# rbccpsiisc_nRF24Cheep.net
KiCad netlist of a schematic drawn in EAGLE
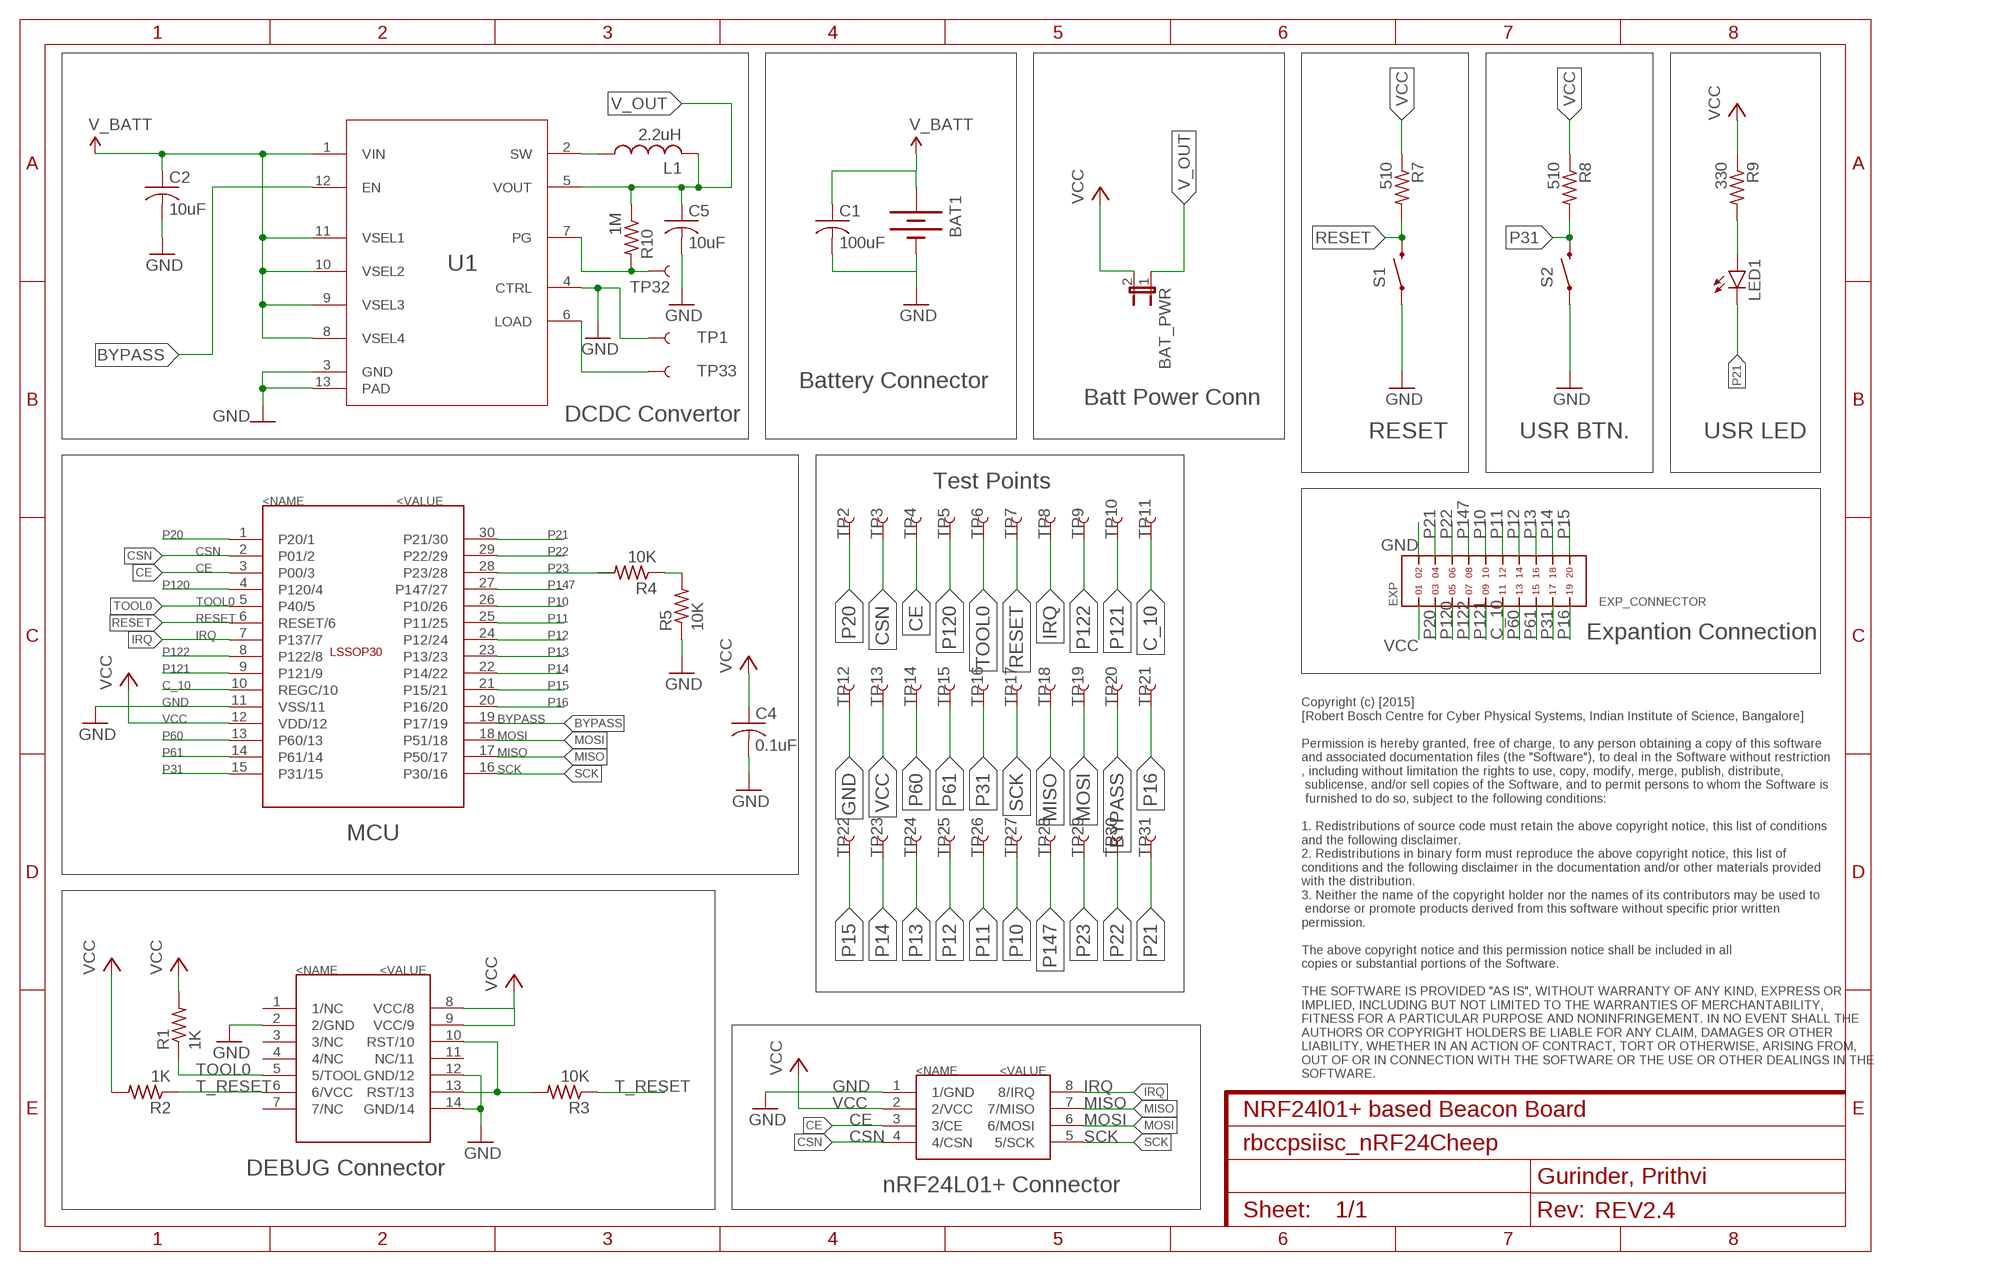
[diagram p0: schematic, sheet 1]

(export (version "E")
  (design (tool "Eeschema 10.0.6"))
  (components
    (comp (ref "BAT1")
      (value "BATTERY20SMD")
      (footprint "eagle-import:BATTCON_20MM")
      (libsource (lib "eagle-import") (part "BATTERY20SMD"))
    )
    (comp (ref "BAT_PWR")
      (value "JUMPER-2PTH")
      (footprint "eagle-import:1X02")
      (libsource (lib "eagle-import") (part "JUMPER-2PTH"))
    )
    (comp (ref "C1")
      (value "100uF")
      (footprint "eagle-import:C1206K")
      (libsource (lib "eagle-import") (part "C-USC1206K"))
    )
    (comp (ref "C2")
      (value "10uF")
      (footprint "eagle-import:C0603K")
      (libsource (lib "eagle-import") (part "C-USC0603K"))
    )
    (comp (ref "C4")
      (value "0.1uF")
      (footprint "eagle-import:C0603K")
      (libsource (lib "eagle-import") (part "C-USC0603K"))
    )
    (comp (ref "C5")
      (value "10uF")
      (footprint "eagle-import:C0603K")
      (libsource (lib "eagle-import") (part "C-USC0603K"))
    )
    (comp (ref "EXP")
      (value "EXP_CONNECTOR")
      (footprint "eagle-import:2X10")
      (libsource (lib "eagle-import") (part "2X10"))
    )
    (comp (ref "L1")
      (value "2.2uH")
      (footprint "eagle-import:L2012C")
      (libsource (lib "eagle-import") (part "L-USL2012C"))
    )
    (comp (ref "LED1")
      (value "LED0603")
      (footprint "eagle-import:LED-0603")
      (libsource (lib "eagle-import") (part "LED0603"))
    )
    (comp (ref "NRFSOCKET")
      (value "BERG_NRF24_NRF24")
      (footprint "eagle-import:BERG_NRF24_NRF24")
      (libsource (lib "eagle-import") (part "BERG_NRF24_NRF24"))
    )
    (comp (ref "R1")
      (value "1K")
      (footprint "eagle-import:R0603")
      (libsource (lib "eagle-import") (part "R-US_R0603"))
    )
    (comp (ref "R2")
      (value "1K")
      (footprint "eagle-import:R0603")
      (libsource (lib "eagle-import") (part "R-US_R0603"))
    )
    (comp (ref "R3")
      (value "10K")
      (footprint "eagle-import:R0603")
      (libsource (lib "eagle-import") (part "R-US_R0603"))
    )
    (comp (ref "R4")
      (value "10K")
      (footprint "eagle-import:R0603")
      (libsource (lib "eagle-import") (part "R-US_R0603"))
    )
    (comp (ref "R5")
      (value "10K")
      (footprint "eagle-import:R0603")
      (libsource (lib "eagle-import") (part "R-US_R0603"))
    )
    (comp (ref "R7")
      (value "510")
      (footprint "eagle-import:R0603")
      (libsource (lib "eagle-import") (part "R-US_R0603"))
    )
    (comp (ref "R8")
      (value "510")
      (footprint "eagle-import:R0603")
      (libsource (lib "eagle-import") (part "R-US_R0603"))
    )
    (comp (ref "R9")
      (value "330")
      (footprint "eagle-import:R0603")
      (libsource (lib "eagle-import") (part "R-US_R0603"))
    )
    (comp (ref "R10")
      (value "1M")
      (footprint "eagle-import:R0603")
      (libsource (lib "eagle-import") (part "R-US_R0603"))
    )
    (comp (ref "RENASENCE")
      (value "SSOP30_SSOP30")
      (footprint "eagle-import:SSOP30_SSOP30")
      (libsource (lib "eagle-import") (part "SSOP30_SSOP30"))
    )
    (comp (ref "S1")
      (value "SWITCH-MOMENTARY-2-SMD-1101NE")
      (footprint "eagle-import:TACTILE-SWITCH-1101NE")
      (libsource (lib "eagle-import") (part "SWITCH-MOMENTARY-2-SMD-1101NE"))
    )
    (comp (ref "S2")
      (value "SWITCH-MOMENTARY-2-SMD-1101NE")
      (footprint "eagle-import:TACTILE-SWITCH-1101NE")
      (libsource (lib "eagle-import") (part "SWITCH-MOMENTARY-2-SMD-1101NE"))
    )
    (comp (ref "TP1")
      (value "TEST-POINT3X4")
      (footprint "eagle-import:PAD.03X.04")
      (libsource (lib "eagle-import") (part "TEST-POINT3X4"))
    )
    (comp (ref "TP2")
      (value "TEST-POINT3X4")
      (footprint "eagle-import:PAD.03X.04")
      (libsource (lib "eagle-import") (part "TEST-POINT3X4"))
    )
    (comp (ref "TP3")
      (value "TEST-POINT3X4")
      (footprint "eagle-import:PAD.03X.04")
      (libsource (lib "eagle-import") (part "TEST-POINT3X4"))
    )
    (comp (ref "TP4")
      (value "TEST-POINT3X4")
      (footprint "eagle-import:PAD.03X.04")
      (libsource (lib "eagle-import") (part "TEST-POINT3X4"))
    )
    (comp (ref "TP5")
      (value "TEST-POINT3X4")
      (footprint "eagle-import:PAD.03X.04")
      (libsource (lib "eagle-import") (part "TEST-POINT3X4"))
    )
    (comp (ref "TP6")
      (value "TEST-POINT3X4")
      (footprint "eagle-import:PAD.03X.04")
      (libsource (lib "eagle-import") (part "TEST-POINT3X4"))
    )
    (comp (ref "TP7")
      (value "TEST-POINT3X4")
      (footprint "eagle-import:PAD.03X.04")
      (libsource (lib "eagle-import") (part "TEST-POINT3X4"))
    )
    (comp (ref "TP8")
      (value "TEST-POINT3X4")
      (footprint "eagle-import:PAD.03X.04")
      (libsource (lib "eagle-import") (part "TEST-POINT3X4"))
    )
    (comp (ref "TP9")
      (value "TEST-POINT3X4")
      (footprint "eagle-import:PAD.03X.04")
      (libsource (lib "eagle-import") (part "TEST-POINT3X4"))
    )
    (comp (ref "TP10")
      (value "TEST-POINT3X4")
      (footprint "eagle-import:PAD.03X.04")
      (libsource (lib "eagle-import") (part "TEST-POINT3X4"))
    )
    (comp (ref "TP11")
      (value "TEST-POINT3X4")
      (footprint "eagle-import:PAD.03X.04")
      (libsource (lib "eagle-import") (part "TEST-POINT3X4"))
    )
    (comp (ref "TP12")
      (value "TEST-POINT3X4")
      (footprint "eagle-import:PAD.03X.04")
      (libsource (lib "eagle-import") (part "TEST-POINT3X4"))
    )
    (comp (ref "TP13")
      (value "TEST-POINT3X4")
      (footprint "eagle-import:PAD.03X.04")
      (libsource (lib "eagle-import") (part "TEST-POINT3X4"))
    )
    (comp (ref "TP14")
      (value "TEST-POINT3X4")
      (footprint "eagle-import:PAD.03X.04")
      (libsource (lib "eagle-import") (part "TEST-POINT3X4"))
    )
    (comp (ref "TP15")
      (value "TEST-POINT3X4")
      (footprint "eagle-import:PAD.03X.04")
      (libsource (lib "eagle-import") (part "TEST-POINT3X4"))
    )
    (comp (ref "TP16")
      (value "TEST-POINT3X4")
      (footprint "eagle-import:PAD.03X.04")
      (libsource (lib "eagle-import") (part "TEST-POINT3X4"))
    )
    (comp (ref "TP17")
      (value "TEST-POINT3X4")
      (footprint "eagle-import:PAD.03X.04")
      (libsource (lib "eagle-import") (part "TEST-POINT3X4"))
    )
    (comp (ref "TP18")
      (value "TEST-POINT3X4")
      (footprint "eagle-import:PAD.03X.04")
      (libsource (lib "eagle-import") (part "TEST-POINT3X4"))
    )
    (comp (ref "TP19")
      (value "TEST-POINT3X4")
      (footprint "eagle-import:PAD.03X.04")
      (libsource (lib "eagle-import") (part "TEST-POINT3X4"))
    )
    (comp (ref "TP20")
      (value "TEST-POINT3X4")
      (footprint "eagle-import:PAD.03X.04")
      (libsource (lib "eagle-import") (part "TEST-POINT3X4"))
    )
    (comp (ref "TP21")
      (value "TEST-POINT3X4")
      (footprint "eagle-import:PAD.03X.04")
      (libsource (lib "eagle-import") (part "TEST-POINT3X4"))
    )
    (comp (ref "TP22")
      (value "TEST-POINT3X4")
      (footprint "eagle-import:PAD.03X.04")
      (libsource (lib "eagle-import") (part "TEST-POINT3X4"))
    )
    (comp (ref "TP23")
      (value "TEST-POINT3X4")
      (footprint "eagle-import:PAD.03X.04")
      (libsource (lib "eagle-import") (part "TEST-POINT3X4"))
    )
    (comp (ref "TP24")
      (value "TEST-POINT3X4")
      (footprint "eagle-import:PAD.03X.04")
      (libsource (lib "eagle-import") (part "TEST-POINT3X4"))
    )
    (comp (ref "TP25")
      (value "TEST-POINT3X4")
      (footprint "eagle-import:PAD.03X.04")
      (libsource (lib "eagle-import") (part "TEST-POINT3X4"))
    )
    (comp (ref "TP26")
      (value "TEST-POINT3X4")
      (footprint "eagle-import:PAD.03X.04")
      (libsource (lib "eagle-import") (part "TEST-POINT3X4"))
    )
    (comp (ref "TP27")
      (value "TEST-POINT3X4")
      (footprint "eagle-import:PAD.03X.04")
      (libsource (lib "eagle-import") (part "TEST-POINT3X4"))
    )
    (comp (ref "TP28")
      (value "TEST-POINT3X4")
      (footprint "eagle-import:PAD.03X.04")
      (libsource (lib "eagle-import") (part "TEST-POINT3X4"))
    )
    (comp (ref "TP29")
      (value "TEST-POINT3X4")
      (footprint "eagle-import:PAD.03X.04")
      (libsource (lib "eagle-import") (part "TEST-POINT3X4"))
    )
    (comp (ref "TP30")
      (value "TEST-POINT3X4")
      (footprint "eagle-import:PAD.03X.04")
      (libsource (lib "eagle-import") (part "TEST-POINT3X4"))
    )
    (comp (ref "TP31")
      (value "TEST-POINT3X4")
      (footprint "eagle-import:PAD.03X.04")
      (libsource (lib "eagle-import") (part "TEST-POINT3X4"))
    )
    (comp (ref "TP32")
      (value "TEST-POINT3X4")
      (footprint "eagle-import:PAD.03X.04")
      (libsource (lib "eagle-import") (part "TEST-POINT3X4"))
    )
    (comp (ref "TP33")
      (value "TEST-POINT3X4")
      (footprint "eagle-import:PAD.03X.04")
      (libsource (lib "eagle-import") (part "TEST-POINT3X4"))
    )
    (comp (ref "U$3")
      (value "BERG_5_BERG_14")
      (footprint "eagle-import:BERG_5_BERG_5")
      (libsource (lib "eagle-import") (part "BERG_5_BERG_14"))
    )
    (comp (ref "U1")
      (value "TPS62740DSST")
      (footprint "eagle-import:DSS0012A")
      (fields
        (field (name "MANUFACTURER") "Texas Instruments")
        (field (name "PARTNUMBER") "TPS62740DSS")
        (field (name "APPROVEDBY") "Not shown in title block")
        (field (name "AUTHOR") "Not shown in title block")
        (field (name "CHECKEDBY") "Not shown in title block")
        (field (name "ENGINEER") "Not shown in title block")
        (field (name "MODIFIEDDATE") "Not shown in title block")
        (field (name "PUBLISHER") "Texas Instruments")
        (field (name "SYMBOLCREATOR") "a0411947")
      )
      (libsource (lib "eagle-import") (part "TPS62740DSST"))
    )
  )
  (nets
    (net (code "1") (name "/T_RESET") (class "Default")
      (node (ref "R2") (pin "1") (pinfunction "1_1") (pintype "passive"))
      (node (ref "R3") (pin "1") (pinfunction "1_1") (pintype "passive"))
      (node (ref "U$3") (pin "6") (pinfunction "6/VCC_6") (pintype "bidirectional"))
    )
    (net (code "2") (name "BYPASS") (class "Default")
      (node (ref "RENASENCE") (pin "19") (pinfunction "P17/19_19") (pintype "bidirectional"))
      (node (ref "TP20") (pin "P$1") (pinfunction "1_P$1") (pintype "bidirectional"))
      (node (ref "U1") (pin "12") (pinfunction "EN_12") (pintype "input"))
    )
    (net (code "3") (name "CE") (class "Default")
      (node (ref "NRFSOCKET") (pin "3") (pinfunction "3/CE_3") (pintype "bidirectional"))
      (node (ref "RENASENCE") (pin "3") (pinfunction "P00/3_3") (pintype "bidirectional"))
      (node (ref "TP4") (pin "P$1") (pinfunction "1_P$1") (pintype "bidirectional"))
    )
    (net (code "4") (name "CSN") (class "Default")
      (node (ref "NRFSOCKET") (pin "4") (pinfunction "4/CSN_4") (pintype "bidirectional"))
      (node (ref "RENASENCE") (pin "2") (pinfunction "P01/2_2") (pintype "bidirectional"))
      (node (ref "TP3") (pin "P$1") (pinfunction "1_P$1") (pintype "bidirectional"))
    )
    (net (code "5") (name "C_10") (class "Default")
      (node (ref "EXP") (pin "11") (pinfunction "11_11") (pintype "bidirectional"))
      (node (ref "RENASENCE") (pin "10") (pinfunction "REGC/10_10") (pintype "bidirectional"))
      (node (ref "TP11") (pin "P$1") (pinfunction "1_P$1") (pintype "bidirectional"))
    )
    (net (code "6") (name "GND") (class "Default")
      (node (ref "BAT1") (pin "2") (pinfunction "-_2") (pintype "power_in"))
      (node (ref "C1") (pin "2") (pinfunction "2_2") (pintype "passive"))
      (node (ref "C2") (pin "2") (pinfunction "2_2") (pintype "passive"))
      (node (ref "C4") (pin "2") (pinfunction "2_2") (pintype "passive"))
      (node (ref "C5") (pin "2") (pinfunction "2_2") (pintype "passive"))
      (node (ref "EXP") (pin "2") (pinfunction "2_2") (pintype "bidirectional"))
      (node (ref "NRFSOCKET") (pin "1") (pinfunction "1/GND_1") (pintype "bidirectional"))
      (node (ref "R5") (pin "1") (pinfunction "1_1") (pintype "passive"))
      (node (ref "RENASENCE") (pin "11") (pinfunction "VSS/11_11") (pintype "bidirectional"))
      (node (ref "S1") (pin "P$1") (pinfunction "1_P$1") (pintype "passive"))
      (node (ref "S2") (pin "P$1") (pinfunction "1_P$1") (pintype "passive"))
      (node (ref "TP1") (pin "P$1") (pinfunction "1_P$1") (pintype "bidirectional"))
      (node (ref "TP12") (pin "P$1") (pinfunction "1_P$1") (pintype "bidirectional"))
      (node (ref "U$3") (pin "12") (pinfunction "GND/12_12") (pintype "bidirectional"))
      (node (ref "U$3") (pin "14") (pinfunction "GND/14_14") (pintype "bidirectional"))
      (node (ref "U$3") (pin "2") (pinfunction "2/GND_2") (pintype "bidirectional"))
      (node (ref "U1") (pin "13") (pinfunction "PAD_13") (pintype "power_in"))
      (node (ref "U1") (pin "3") (pinfunction "GND_3") (pintype "power_in"))
      (node (ref "U1") (pin "4") (pinfunction "CTRL_4") (pintype "input"))
    )
    (net (code "7") (name "IRQ") (class "Default")
      (node (ref "NRFSOCKET") (pin "8") (pinfunction "8/IRQ_8") (pintype "bidirectional"))
      (node (ref "RENASENCE") (pin "7") (pinfunction "P137/7_7") (pintype "bidirectional"))
      (node (ref "TP8") (pin "P$1") (pinfunction "1_P$1") (pintype "bidirectional"))
    )
    (net (code "8") (name "MISO") (class "Default")
      (node (ref "NRFSOCKET") (pin "7") (pinfunction "7/MISO_7") (pintype "bidirectional"))
      (node (ref "RENASENCE") (pin "17") (pinfunction "P50/17_17") (pintype "bidirectional"))
      (node (ref "TP18") (pin "P$1") (pinfunction "1_P$1") (pintype "bidirectional"))
    )
    (net (code "9") (name "MOSI") (class "Default")
      (node (ref "NRFSOCKET") (pin "6") (pinfunction "6/MOSI_6") (pintype "bidirectional"))
      (node (ref "RENASENCE") (pin "18") (pinfunction "P51/18_18") (pintype "bidirectional"))
      (node (ref "TP19") (pin "P$1") (pinfunction "1_P$1") (pintype "bidirectional"))
    )
    (net (code "10") (name "Net-(LED1-PadA)") (class "Default")
      (node (ref "LED1") (pin "A") (pinfunction "A_A") (pintype "passive"))
      (node (ref "R9") (pin "2") (pinfunction "2_2") (pintype "passive"))
    )
    (net (code "11") (name "Net-(R4-Pad1)") (class "Default")
      (node (ref "R4") (pin "1") (pinfunction "1_1") (pintype "passive"))
      (node (ref "R5") (pin "2") (pinfunction "2_2") (pintype "passive"))
    )
    (net (code "12") (name "Net-(TP32-1)") (class "Default")
      (node (ref "R10") (pin "2") (pinfunction "2_2") (pintype "passive"))
      (node (ref "TP32") (pin "P$1") (pinfunction "1_P$1") (pintype "bidirectional"))
      (node (ref "U1") (pin "7") (pinfunction "PG_7") (pintype "output"))
    )
    (net (code "13") (name "Net-(TP33-1)") (class "Default")
      (node (ref "TP33") (pin "P$1") (pinfunction "1_P$1") (pintype "bidirectional"))
      (node (ref "U1") (pin "6") (pinfunction "LOAD_6") (pintype "power_in"))
    )
    (net (code "14") (name "Net-(U1-SW)") (class "Default")
      (node (ref "L1") (pin "1") (pinfunction "1_1") (pintype "passive"))
      (node (ref "U1") (pin "2") (pinfunction "SW_2") (pintype "power_in"))
    )
    (net (code "15") (name "P10") (class "Default")
      (node (ref "EXP") (pin "10") (pinfunction "10_10") (pintype "bidirectional"))
      (node (ref "RENASENCE") (pin "26") (pinfunction "P10/26_26") (pintype "bidirectional"))
      (node (ref "TP27") (pin "P$1") (pinfunction "1_P$1") (pintype "bidirectional"))
    )
    (net (code "16") (name "P11") (class "Default")
      (node (ref "EXP") (pin "12") (pinfunction "12_12") (pintype "bidirectional"))
      (node (ref "RENASENCE") (pin "25") (pinfunction "P11/25_25") (pintype "bidirectional"))
      (node (ref "TP26") (pin "P$1") (pinfunction "1_P$1") (pintype "bidirectional"))
    )
    (net (code "17") (name "P12") (class "Default")
      (node (ref "EXP") (pin "14") (pinfunction "14_14") (pintype "bidirectional"))
      (node (ref "RENASENCE") (pin "24") (pinfunction "P12/24_24") (pintype "bidirectional"))
      (node (ref "TP25") (pin "P$1") (pinfunction "1_P$1") (pintype "bidirectional"))
    )
    (net (code "18") (name "P13") (class "Default")
      (node (ref "EXP") (pin "16") (pinfunction "16_16") (pintype "bidirectional"))
      (node (ref "RENASENCE") (pin "23") (pinfunction "P13/23_23") (pintype "bidirectional"))
      (node (ref "TP24") (pin "P$1") (pinfunction "1_P$1") (pintype "bidirectional"))
    )
    (net (code "19") (name "P14") (class "Default")
      (node (ref "EXP") (pin "18") (pinfunction "18_18") (pintype "bidirectional"))
      (node (ref "RENASENCE") (pin "22") (pinfunction "P14/22_22") (pintype "bidirectional"))
      (node (ref "TP23") (pin "P$1") (pinfunction "1_P$1") (pintype "bidirectional"))
    )
    (net (code "20") (name "P15") (class "Default")
      (node (ref "EXP") (pin "20") (pinfunction "20_20") (pintype "bidirectional"))
      (node (ref "RENASENCE") (pin "21") (pinfunction "P15/21_21") (pintype "bidirectional"))
      (node (ref "TP22") (pin "P$1") (pinfunction "1_P$1") (pintype "bidirectional"))
    )
    (net (code "21") (name "P16") (class "Default")
      (node (ref "EXP") (pin "19") (pinfunction "19_19") (pintype "bidirectional"))
      (node (ref "RENASENCE") (pin "20") (pinfunction "P16/20_20") (pintype "bidirectional"))
      (node (ref "TP21") (pin "P$1") (pinfunction "1_P$1") (pintype "bidirectional"))
    )
    (net (code "22") (name "P20") (class "Default")
      (node (ref "EXP") (pin "3") (pinfunction "3_3") (pintype "bidirectional"))
      (node (ref "RENASENCE") (pin "1") (pinfunction "P20/1_1") (pintype "bidirectional"))
      (node (ref "TP2") (pin "P$1") (pinfunction "1_P$1") (pintype "bidirectional"))
    )
    (net (code "23") (name "P21") (class "Default")
      (node (ref "EXP") (pin "4") (pinfunction "4_4") (pintype "bidirectional"))
      (node (ref "LED1") (pin "C") (pinfunction "C_C") (pintype "passive"))
      (node (ref "RENASENCE") (pin "30") (pinfunction "P21/30_30") (pintype "bidirectional"))
      (node (ref "TP31") (pin "P$1") (pinfunction "1_P$1") (pintype "bidirectional"))
    )
    (net (code "24") (name "P22") (class "Default")
      (node (ref "EXP") (pin "6") (pinfunction "6_6") (pintype "bidirectional"))
      (node (ref "RENASENCE") (pin "29") (pinfunction "P22/29_29") (pintype "bidirectional"))
      (node (ref "TP30") (pin "P$1") (pinfunction "1_P$1") (pintype "bidirectional"))
    )
    (net (code "25") (name "P23") (class "Default")
      (node (ref "R4") (pin "2") (pinfunction "2_2") (pintype "passive"))
      (node (ref "RENASENCE") (pin "28") (pinfunction "P23/28_28") (pintype "bidirectional"))
      (node (ref "TP29") (pin "P$1") (pinfunction "1_P$1") (pintype "bidirectional"))
    )
    (net (code "26") (name "P31") (class "Default")
      (node (ref "EXP") (pin "17") (pinfunction "17_17") (pintype "bidirectional"))
      (node (ref "R8") (pin "2") (pinfunction "2_2") (pintype "passive"))
      (node (ref "RENASENCE") (pin "15") (pinfunction "P31/15_15") (pintype "bidirectional"))
      (node (ref "S2") (pin "P$2") (pinfunction "2_P$2") (pintype "passive"))
      (node (ref "TP16") (pin "P$1") (pinfunction "1_P$1") (pintype "bidirectional"))
    )
    (net (code "27") (name "P60") (class "Default")
      (node (ref "EXP") (pin "13") (pinfunction "13_13") (pintype "bidirectional"))
      (node (ref "RENASENCE") (pin "13") (pinfunction "P60/13_13") (pintype "bidirectional"))
      (node (ref "TP14") (pin "P$1") (pinfunction "1_P$1") (pintype "bidirectional"))
    )
    (net (code "28") (name "P61") (class "Default")
      (node (ref "EXP") (pin "15") (pinfunction "15_15") (pintype "bidirectional"))
      (node (ref "RENASENCE") (pin "14") (pinfunction "P61/14_14") (pintype "bidirectional"))
      (node (ref "TP15") (pin "P$1") (pinfunction "1_P$1") (pintype "bidirectional"))
    )
    (net (code "29") (name "P120") (class "Default")
      (node (ref "EXP") (pin "5") (pinfunction "5_5") (pintype "bidirectional"))
      (node (ref "RENASENCE") (pin "4") (pinfunction "P120/4_4") (pintype "bidirectional"))
      (node (ref "TP5") (pin "P$1") (pinfunction "1_P$1") (pintype "bidirectional"))
    )
    (net (code "30") (name "P121") (class "Default")
      (node (ref "EXP") (pin "9") (pinfunction "9_9") (pintype "bidirectional"))
      (node (ref "RENASENCE") (pin "9") (pinfunction "P121/9_9") (pintype "bidirectional"))
      (node (ref "TP10") (pin "P$1") (pinfunction "1_P$1") (pintype "bidirectional"))
    )
    (net (code "31") (name "P122") (class "Default")
      (node (ref "EXP") (pin "7") (pinfunction "7_7") (pintype "bidirectional"))
      (node (ref "RENASENCE") (pin "8") (pinfunction "P122/8_8") (pintype "bidirectional"))
      (node (ref "TP9") (pin "P$1") (pinfunction "1_P$1") (pintype "bidirectional"))
    )
    (net (code "32") (name "P147") (class "Default")
      (node (ref "EXP") (pin "8") (pinfunction "8_8") (pintype "bidirectional"))
      (node (ref "RENASENCE") (pin "27") (pinfunction "P147/27_27") (pintype "bidirectional"))
      (node (ref "TP28") (pin "P$1") (pinfunction "1_P$1") (pintype "bidirectional"))
    )
    (net (code "33") (name "RESET") (class "Default")
      (node (ref "R3") (pin "2") (pinfunction "2_2") (pintype "passive"))
      (node (ref "R7") (pin "2") (pinfunction "2_2") (pintype "passive"))
      (node (ref "RENASENCE") (pin "6") (pinfunction "RESET/6_6") (pintype "bidirectional"))
      (node (ref "S1") (pin "P$2") (pinfunction "2_P$2") (pintype "passive"))
      (node (ref "TP7") (pin "P$1") (pinfunction "1_P$1") (pintype "bidirectional"))
      (node (ref "U$3") (pin "10") (pinfunction "RST/10_10") (pintype "bidirectional"))
      (node (ref "U$3") (pin "13") (pinfunction "RST/13_13") (pintype "bidirectional"))
    )
    (net (code "34") (name "SCK") (class "Default")
      (node (ref "NRFSOCKET") (pin "5") (pinfunction "5/SCK_5") (pintype "bidirectional"))
      (node (ref "RENASENCE") (pin "16") (pinfunction "P30/16_16") (pintype "bidirectional"))
      (node (ref "TP17") (pin "P$1") (pinfunction "1_P$1") (pintype "bidirectional"))
    )
    (net (code "35") (name "TOOL0") (class "Default")
      (node (ref "R1") (pin "1") (pinfunction "1_1") (pintype "passive"))
      (node (ref "RENASENCE") (pin "5") (pinfunction "P40/5_5") (pintype "bidirectional"))
      (node (ref "TP6") (pin "P$1") (pinfunction "1_P$1") (pintype "bidirectional"))
      (node (ref "U$3") (pin "5") (pinfunction "5/TOOL_5") (pintype "bidirectional"))
    )
    (net (code "36") (name "VCC") (class "Default")
      (node (ref "BAT_PWR") (pin "2") (pinfunction "2_2") (pintype "passive"))
      (node (ref "C4") (pin "1") (pinfunction "1_1") (pintype "passive"))
      (node (ref "EXP") (pin "1") (pinfunction "1_1") (pintype "bidirectional"))
      (node (ref "NRFSOCKET") (pin "2") (pinfunction "2/VCC_2") (pintype "bidirectional"))
      (node (ref "R1") (pin "2") (pinfunction "2_2") (pintype "passive"))
      (node (ref "R2") (pin "2") (pinfunction "2_2") (pintype "passive"))
      (node (ref "R7") (pin "1") (pinfunction "1_1") (pintype "passive"))
      (node (ref "R8") (pin "1") (pinfunction "1_1") (pintype "passive"))
      (node (ref "R9") (pin "1") (pinfunction "1_1") (pintype "passive"))
      (node (ref "RENASENCE") (pin "12") (pinfunction "VDD/12_12") (pintype "bidirectional"))
      (node (ref "TP13") (pin "P$1") (pinfunction "1_P$1") (pintype "bidirectional"))
      (node (ref "U$3") (pin "8") (pinfunction "VCC/8_8") (pintype "bidirectional"))
      (node (ref "U$3") (pin "9") (pinfunction "VCC/9_9") (pintype "bidirectional"))
    )
    (net (code "37") (name "V_BATT") (class "Default")
      (node (ref "BAT1") (pin "1") (pinfunction "+_1") (pintype "power_in"))
      (node (ref "C1") (pin "1") (pinfunction "1_1") (pintype "passive"))
      (node (ref "C2") (pin "1") (pinfunction "1_1") (pintype "passive"))
      (node (ref "U1") (pin "1") (pinfunction "VIN_1") (pintype "power_in"))
      (node (ref "U1") (pin "10") (pinfunction "VSEL2_10") (pintype "input"))
      (node (ref "U1") (pin "11") (pinfunction "VSEL1_11") (pintype "input"))
      (node (ref "U1") (pin "8") (pinfunction "VSEL4_8") (pintype "input"))
      (node (ref "U1") (pin "9") (pinfunction "VSEL3_9") (pintype "input"))
    )
    (net (code "38") (name "V_OUT") (class "Default")
      (node (ref "BAT_PWR") (pin "1") (pinfunction "1_1") (pintype "passive"))
      (node (ref "C5") (pin "1") (pinfunction "1_1") (pintype "passive"))
      (node (ref "L1") (pin "2") (pinfunction "2_2") (pintype "passive"))
      (node (ref "R10") (pin "1") (pinfunction "1_1") (pintype "passive"))
      (node (ref "U1") (pin "5") (pinfunction "VOUT_5") (pintype "input"))
    )
    (net (code "39") (name "unconnected-(U$3-1{slash}NC-Pad1)") (class "Default")
      (node (ref "U$3") (pin "1") (pinfunction "1/NC_1") (pintype "bidirectional"))
    )
    (net (code "40") (name "unconnected-(U$3-3{slash}NC-Pad3)") (class "Default")
      (node (ref "U$3") (pin "3") (pinfunction "3/NC_3") (pintype "bidirectional"))
    )
    (net (code "41") (name "unconnected-(U$3-4{slash}NC-Pad4)") (class "Default")
      (node (ref "U$3") (pin "4") (pinfunction "4/NC_4") (pintype "bidirectional"))
    )
    (net (code "42") (name "unconnected-(U$3-7{slash}NC-Pad7)") (class "Default")
      (node (ref "U$3") (pin "7") (pinfunction "7/NC_7") (pintype "bidirectional"))
    )
    (net (code "43") (name "unconnected-(U$3-NC{slash}11-Pad11)") (class "Default")
      (node (ref "U$3") (pin "11") (pinfunction "NC/11_11") (pintype "bidirectional"))
    )
  )
)
